# Digital_SRAM.net
KiCad netlist of a schematic drawn in Altium Designer
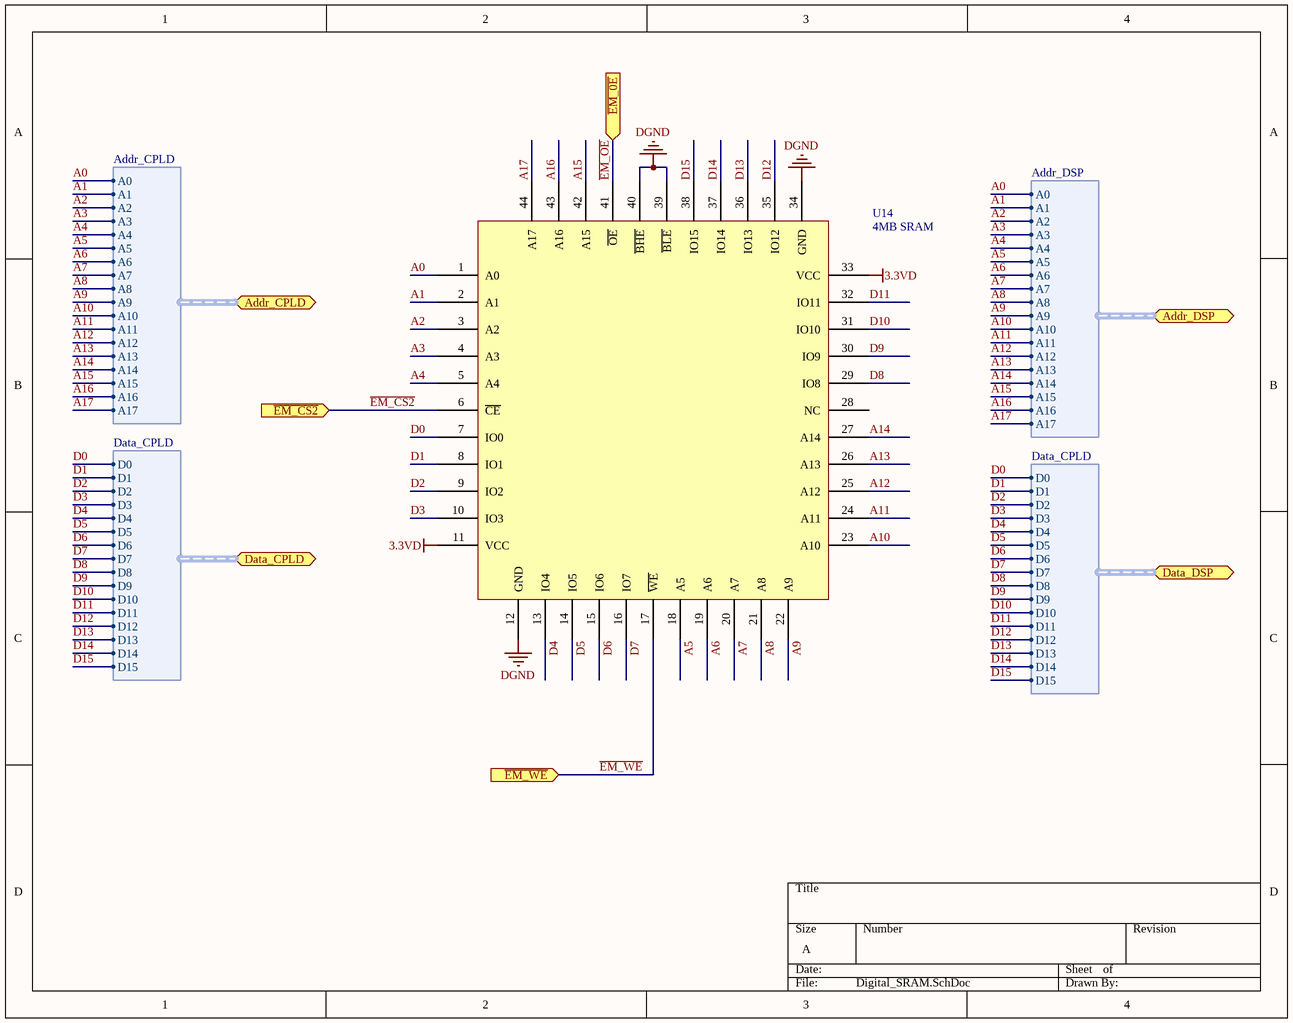
[diagram p0: Digital_SRAM.SchDoc]

(export (version "E")
  (design (tool "Eeschema 10.0.6"))
  (components
    (comp (ref "U14")
      (value "4MB SRAM")
      (footprint "TSOP-44")
      (description "IC SRAM 4MBIT 8NS 44TSOP")
      (libsource (lib "SubjuGator8") (part "CY7C1041CV33-8ZSXI"))
    )
  )
  (nets
    (net (code "4") (name "/A0") (class "Default")
      (node (ref "U14") (pin "1") (pinfunction "A0_1") (pintype "passive"))
    )
    (net (code "5") (name "/A1") (class "Default")
      (node (ref "U14") (pin "2") (pinfunction "A1_2") (pintype "passive"))
    )
    (net (code "6") (name "/A2") (class "Default")
      (node (ref "U14") (pin "3") (pinfunction "A2_3") (pintype "passive"))
    )
    (net (code "7") (name "/A3") (class "Default")
      (node (ref "U14") (pin "4") (pinfunction "A3_4") (pintype "passive"))
    )
    (net (code "8") (name "/A4") (class "Default")
      (node (ref "U14") (pin "5") (pinfunction "A4_5") (pintype "passive"))
    )
    (net (code "9") (name "/A5") (class "Default")
      (node (ref "U14") (pin "18") (pinfunction "A5_18") (pintype "passive"))
    )
    (net (code "10") (name "/A6") (class "Default")
      (node (ref "U14") (pin "19") (pinfunction "A6_19") (pintype "passive"))
    )
    (net (code "11") (name "/A7") (class "Default")
      (node (ref "U14") (pin "20") (pinfunction "A7_20") (pintype "passive"))
    )
    (net (code "12") (name "/A8") (class "Default")
      (node (ref "U14") (pin "21") (pinfunction "A8_21") (pintype "passive"))
    )
    (net (code "13") (name "/A9") (class "Default")
      (node (ref "U14") (pin "22") (pinfunction "A9_22") (pintype "passive"))
    )
    (net (code "14") (name "/A10") (class "Default")
      (node (ref "U14") (pin "23") (pinfunction "A10_23") (pintype "passive"))
    )
    (net (code "15") (name "/A11") (class "Default")
      (node (ref "U14") (pin "24") (pinfunction "A11_24") (pintype "passive"))
    )
    (net (code "16") (name "/A12") (class "Default")
      (node (ref "U14") (pin "25") (pinfunction "A12_25") (pintype "passive"))
    )
    (net (code "17") (name "/A13") (class "Default")
      (node (ref "U14") (pin "26") (pinfunction "A13_26") (pintype "passive"))
    )
    (net (code "18") (name "/A14") (class "Default")
      (node (ref "U14") (pin "27") (pinfunction "A14_27") (pintype "passive"))
    )
    (net (code "19") (name "/A15") (class "Default")
      (node (ref "U14") (pin "42") (pinfunction "A15_42") (pintype "passive"))
    )
    (net (code "20") (name "/A16") (class "Default")
      (node (ref "U14") (pin "43") (pinfunction "A16_43") (pintype "passive"))
    )
    (net (code "21") (name "/A17") (class "Default")
      (node (ref "U14") (pin "44") (pinfunction "A17_44") (pintype "passive"))
    )
    (net (code "22") (name "/D0") (class "Default")
      (node (ref "U14") (pin "7") (pinfunction "IO0_7") (pintype "passive"))
    )
    (net (code "23") (name "/D1") (class "Default")
      (node (ref "U14") (pin "8") (pinfunction "IO1_8") (pintype "passive"))
    )
    (net (code "24") (name "/D2") (class "Default")
      (node (ref "U14") (pin "9") (pinfunction "IO2_9") (pintype "passive"))
    )
    (net (code "25") (name "/D3") (class "Default")
      (node (ref "U14") (pin "10") (pinfunction "IO3_10") (pintype "passive"))
    )
    (net (code "26") (name "/D4") (class "Default")
      (node (ref "U14") (pin "13") (pinfunction "IO4_13") (pintype "passive"))
    )
    (net (code "27") (name "/D5") (class "Default")
      (node (ref "U14") (pin "14") (pinfunction "IO5_14") (pintype "passive"))
    )
    (net (code "28") (name "/D6") (class "Default")
      (node (ref "U14") (pin "15") (pinfunction "IO6_15") (pintype "passive"))
    )
    (net (code "29") (name "/D7") (class "Default")
      (node (ref "U14") (pin "16") (pinfunction "IO7_16") (pintype "passive"))
    )
    (net (code "30") (name "/D8") (class "Default")
      (node (ref "U14") (pin "29") (pinfunction "IO8_29") (pintype "passive"))
    )
    (net (code "31") (name "/D9") (class "Default")
      (node (ref "U14") (pin "30") (pinfunction "IO9_30") (pintype "passive"))
    )
    (net (code "32") (name "/D10") (class "Default")
      (node (ref "U14") (pin "31") (pinfunction "IO10_31") (pintype "passive"))
    )
    (net (code "33") (name "/D11") (class "Default")
      (node (ref "U14") (pin "32") (pinfunction "IO11_32") (pintype "passive"))
    )
    (net (code "34") (name "/D12") (class "Default")
      (node (ref "U14") (pin "35") (pinfunction "IO12_35") (pintype "passive"))
    )
    (net (code "35") (name "/D13") (class "Default")
      (node (ref "U14") (pin "36") (pinfunction "IO13_36") (pintype "passive"))
    )
    (net (code "36") (name "/D14") (class "Default")
      (node (ref "U14") (pin "37") (pinfunction "IO14_37") (pintype "passive"))
    )
    (net (code "37") (name "/D15") (class "Default")
      (node (ref "U14") (pin "38") (pinfunction "IO15_38") (pintype "passive"))
    )
    (net (code "41") (name "/~{EM_CS2}") (class "Default")
      (node (ref "U14") (pin "6") (pinfunction "~{CE}_6") (pintype "passive"))
    )
    (net (code "42") (name "/~{EM_OE}") (class "Default")
      (node (ref "U14") (pin "41") (pinfunction "~{OE}_41") (pintype "passive"))
    )
    (net (code "43") (name "/~{EM_WE}") (class "Default")
      (node (ref "U14") (pin "17") (pinfunction "~{WE}_17") (pintype "passive"))
    )
    (net (code "44") (name "3.3VD") (class "Default")
      (node (ref "U14") (pin "11") (pinfunction "VCC_11") (pintype "passive"))
      (node (ref "U14") (pin "33") (pinfunction "VCC_33") (pintype "passive"))
    )
    (net (code "45") (name "DGND") (class "Default")
      (node (ref "U14") (pin "12") (pinfunction "GND_12") (pintype "passive"))
      (node (ref "U14") (pin "34") (pinfunction "GND_34") (pintype "passive"))
      (node (ref "U14") (pin "39") (pinfunction "~{BLE}_39") (pintype "passive"))
      (node (ref "U14") (pin "40") (pinfunction "~{BHE}_40") (pintype "passive"))
    )
    (net (code "46") (name "unconnected-(U14-NC-Pad28)") (class "Default")
      (node (ref "U14") (pin "28") (pinfunction "NC_28") (pintype "passive"))
    )
  )
)
